# WL-CONNECT.net
KiCad netlist of a schematic drawn in Altium Designer
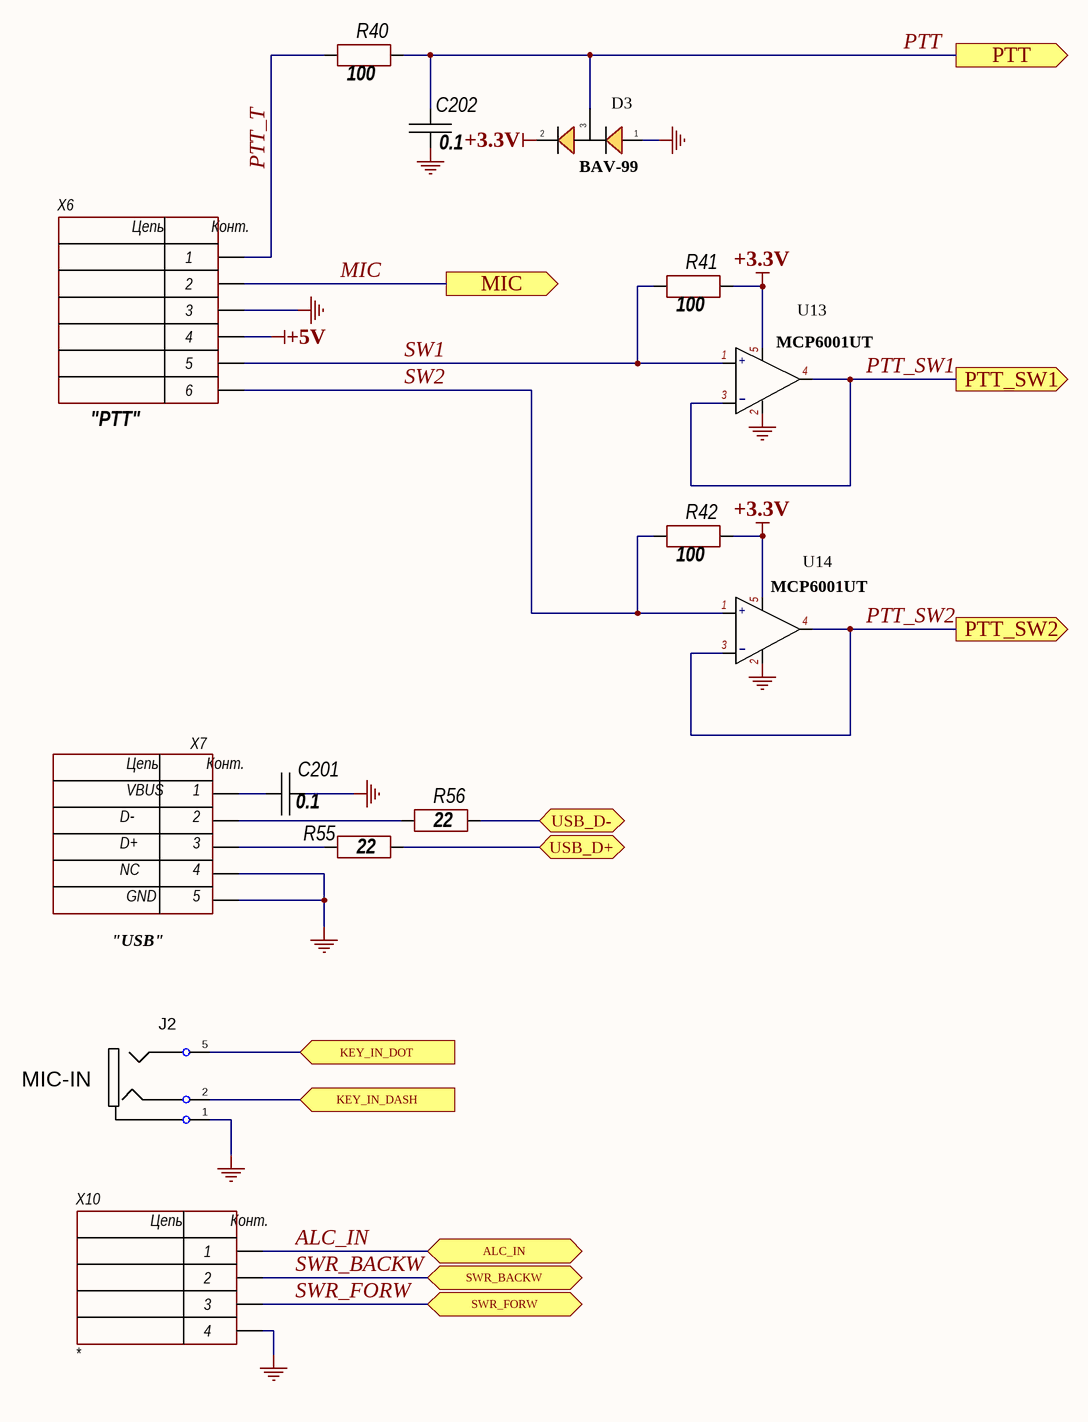
[diagram p0: WL-CONNECT.SchDoc]

(export (version "E")
  (design (tool "Eeschema 10.0.6"))
  (components
    (comp (ref "C201")
      (value "0.1")
      (footprint "standard:CH0805C")
      (libsource (lib "Discrete") (part "Capacitor"))
    )
    (comp (ref "C202")
      (value "0.1")
      (footprint "standard:CH0805C")
      (libsource (lib "Discrete") (part "Capacitor"))
    )
    (comp (ref "D3")
      (value "BAV-99")
      (footprint "standard:SOT23_132")
      (libsource (lib "Analog") (part "BAV-99"))
    )
    (comp (ref "J2")
      (value "MIC-IN")
      (footprint "3.5-stereo")
      (description "SJ1-3525NG")
      (libsource (lib "*") (part "SJ1-3523N"))
    )
    (comp (ref "R40")
      (value "100")
      (footprint "standard:CH0805R")
      (libsource (lib "Discrete") (part "Resistor"))
    )
    (comp (ref "R41")
      (value "100")
      (footprint "standard:CH0805R")
      (libsource (lib "Discrete") (part "Resistor"))
    )
    (comp (ref "R42")
      (value "100")
      (footprint "standard:CH0805R")
      (libsource (lib "Discrete") (part "Resistor"))
    )
    (comp (ref "R55")
      (value "22")
      (footprint "standard:CH0805R")
      (libsource (lib "Discrete") (part "Resistor"))
    )
    (comp (ref "R56")
      (value "22")
      (footprint "standard:CH0805R")
      (libsource (lib "Discrete") (part "Resistor"))
    )
    (comp (ref "U13")
      (value "MCP6001UT")
      (footprint "SOT23-5")
      (libsource (lib "Analog") (part "MCP6001UT_1"))
    )
    (comp (ref "U14")
      (value "MCP6001UT")
      (footprint "SOT23-5")
      (libsource (lib "Analog") (part "MCP6001UT_1"))
    )
    (comp (ref "X6")
      (value "\"PTT\"")
      (footprint "RJ25-6pin")
      (libsource (lib "Connectors") (part "6-Connector"))
    )
    (comp (ref "X7")
      (value "\"USB\"")
      (footprint "USB-mini")
      (description "USB")
      (libsource (lib "Connectors") (part "miniUSB-B"))
    )
    (comp (ref "X10")
      (value "*")
      (footprint "custom:CON: PLS-4")
      (libsource (lib "Connectors") (part "4-Connector"))
    )
  )
  (nets
    (net (code "1") (name "+3.3V") (class "Default")
      (node (ref "D3") (pin "2") (pinfunction "1_2") (pintype "passive"))
      (node (ref "R41") (pin "2") (pinfunction "2_2") (pintype "passive"))
      (node (ref "R42") (pin "2") (pinfunction "2_2") (pintype "passive"))
      (node (ref "U13") (pin "5") (pinfunction "5_5") (pintype "passive"))
      (node (ref "U14") (pin "5") (pinfunction "5_5") (pintype "passive"))
    )
    (net (code "2") (name "+5V") (class "Default")
      (node (ref "X6") (pin "4") (pinfunction "4_4") (pintype "power_in"))
    )
    (net (code "3") (name "/ALC_IN") (class "Default")
      (node (ref "X10") (pin "1") (pinfunction "1_1") (pintype "passive"))
    )
    (net (code "4") (name "/KEY_IN_DASH") (class "Default")
      (node (ref "J2") (pin "2") (pinfunction "5_2") (pintype "passive"))
    )
    (net (code "5") (name "/KEY_IN_DOT") (class "Default")
      (node (ref "J2") (pin "5") (pinfunction "2_5") (pintype "passive"))
    )
    (net (code "6") (name "/MIC") (class "Default")
      (node (ref "X6") (pin "2") (pinfunction "2_2") (pintype "passive"))
    )
    (net (code "7") (name "/PTT") (class "Default")
      (node (ref "C202") (pin "2") (pinfunction "2_2") (pintype "power_in"))
      (node (ref "D3") (pin "3") (pinfunction "3_3") (pintype "passive"))
      (node (ref "R40") (pin "2") (pinfunction "2_2") (pintype "passive"))
    )
    (net (code "8") (name "/PTT_SW1") (class "Default")
      (node (ref "U13") (pin "3") (pinfunction "3_3") (pintype "passive"))
      (node (ref "U13") (pin "4") (pinfunction "4_4") (pintype "passive"))
    )
    (net (code "9") (name "/PTT_SW2") (class "Default")
      (node (ref "U14") (pin "3") (pinfunction "3_3") (pintype "passive"))
      (node (ref "U14") (pin "4") (pinfunction "4_4") (pintype "passive"))
    )
    (net (code "10") (name "/PTT_T") (class "Default")
      (node (ref "R40") (pin "1") (pinfunction "1_1") (pintype "passive"))
      (node (ref "X6") (pin "1") (pinfunction "1_1") (pintype "passive"))
    )
    (net (code "11") (name "/SW1") (class "Default")
      (node (ref "R41") (pin "1") (pinfunction "1_1") (pintype "passive"))
      (node (ref "U13") (pin "1") (pinfunction "1_1") (pintype "passive"))
      (node (ref "X6") (pin "5") (pinfunction "5_5") (pintype "power_in"))
    )
    (net (code "12") (name "/SW2") (class "Default")
      (node (ref "R42") (pin "1") (pinfunction "1_1") (pintype "passive"))
      (node (ref "U14") (pin "1") (pinfunction "1_1") (pintype "passive"))
      (node (ref "X6") (pin "6") (pinfunction "6_6") (pintype "power_in"))
    )
    (net (code "13") (name "/SWR_BACKW") (class "Default")
      (node (ref "X10") (pin "2") (pinfunction "2_2") (pintype "passive"))
    )
    (net (code "14") (name "/SWR_FORW") (class "Default")
      (node (ref "X10") (pin "3") (pinfunction "3_3") (pintype "power_in"))
    )
    (net (code "15") (name "/USB_D+") (class "Default")
      (node (ref "R55") (pin "2") (pinfunction "2_2") (pintype "passive"))
    )
    (net (code "16") (name "/USB_D-") (class "Default")
      (node (ref "R56") (pin "2") (pinfunction "2_2") (pintype "passive"))
    )
    (net (code "17") (name "GND") (class "Default")
      (node (ref "C201") (pin "2") (pinfunction "2_2") (pintype "power_in"))
      (node (ref "C202") (pin "1") (pinfunction "1_1") (pintype "power_in"))
      (node (ref "D3") (pin "1") (pinfunction "1_1") (pintype "passive"))
      (node (ref "J2") (pin "1") (pinfunction "1_1") (pintype "passive"))
      (node (ref "U13") (pin "2") (pinfunction "2_2") (pintype "passive"))
      (node (ref "U14") (pin "2") (pinfunction "2_2") (pintype "passive"))
      (node (ref "X10") (pin "4") (pinfunction "4_4") (pintype "power_in"))
      (node (ref "X6") (pin "3") (pinfunction "3_3") (pintype "power_in"))
      (node (ref "X7") (pin "4") (pinfunction "4_4") (pintype "passive"))
      (node (ref "X7") (pin "5") (pinfunction "5_5") (pintype "passive"))
    )
    (net (code "18") (name "Net-(C201-Pad1)") (class "Default")
      (node (ref "C201") (pin "1") (pinfunction "1_1") (pintype "power_in"))
      (node (ref "X7") (pin "1") (pintype "passive"))
    )
    (net (code "19") (name "Net-(R55-Pad1)") (class "Default")
      (node (ref "R55") (pin "1") (pinfunction "1_1") (pintype "passive"))
      (node (ref "X7") (pin "3") (pinfunction "3_3") (pintype "passive"))
    )
    (net (code "20") (name "Net-(R56-Pad1)") (class "Default")
      (node (ref "R56") (pin "1") (pinfunction "1_1") (pintype "passive"))
      (node (ref "X7") (pin "2") (pinfunction "2_2") (pintype "passive"))
    )
  )
)
